# Analog_Input.net
KiCad netlist of a schematic drawn in Altium Designer
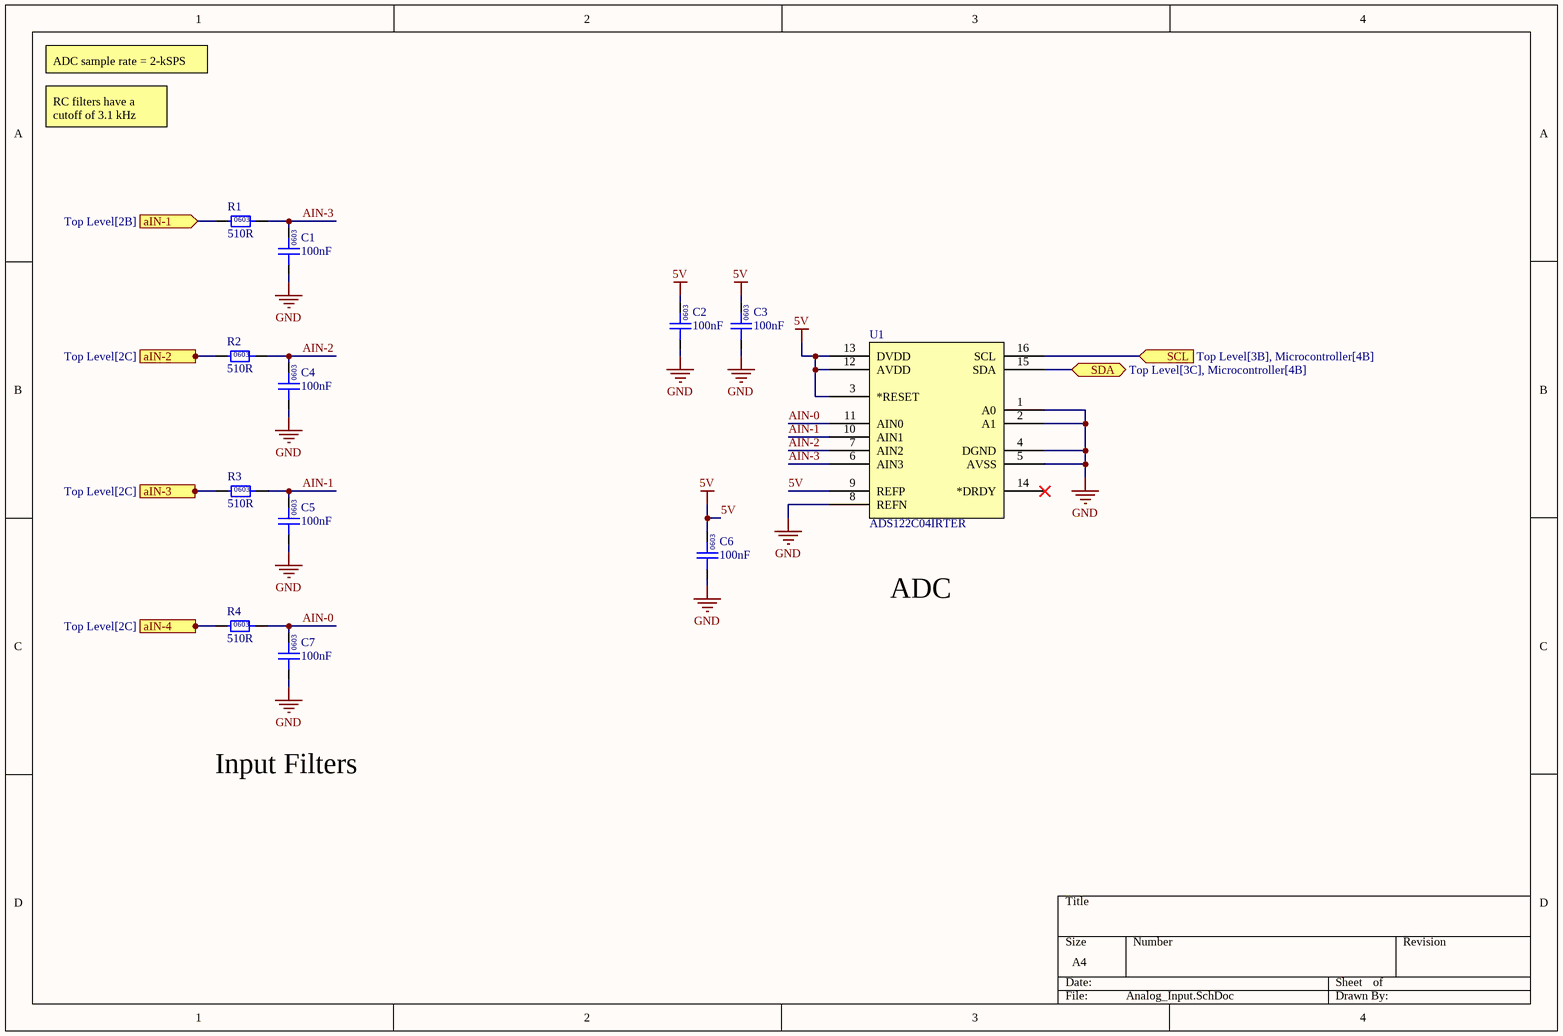
[diagram p0: Analog_Input.SchDoc]

(export (version "E")
  (design (tool "Eeschema 10.0.6"))
  (components
    (comp (ref "C1")
      (value "100nF")
      (footprint "0603")
      (fields
        (field (name "PART NUMBER") "GCM188L81H104KA57D")
        (field (name "MANUFACTURER") "muRata")
        (field (name "TOLERANCE") "±10%")
      )
      (libsource (lib "ts_standard_library") (part "Capacitor 0603"))
    )
    (comp (ref "C2")
      (value "100nF")
      (footprint "0603")
      (fields
        (field (name "PART NUMBER") "GCM188L81H104KA57D")
        (field (name "MANUFACTURER") "muRata")
        (field (name "TOLERANCE") "±10%")
      )
      (libsource (lib "ts_standard_library") (part "Capacitor 0603"))
    )
    (comp (ref "C3")
      (value "100nF")
      (footprint "0603")
      (fields
        (field (name "PART NUMBER") "GCM188L81H104KA57D")
        (field (name "MANUFACTURER") "muRata")
        (field (name "TOLERANCE") "±10%")
      )
      (libsource (lib "ts_standard_library") (part "Capacitor 0603"))
    )
    (comp (ref "C4")
      (value "100nF")
      (footprint "0603")
      (fields
        (field (name "PART NUMBER") "GCM188L81H104KA57D")
        (field (name "MANUFACTURER") "muRata")
        (field (name "TOLERANCE") "±10%")
      )
      (libsource (lib "ts_standard_library") (part "Capacitor 0603"))
    )
    (comp (ref "C5")
      (value "100nF")
      (footprint "0603")
      (fields
        (field (name "PART NUMBER") "GCM188L81H104KA57D")
        (field (name "MANUFACTURER") "muRata")
        (field (name "TOLERANCE") "±10%")
      )
      (libsource (lib "ts_standard_library") (part "Capacitor 0603"))
    )
    (comp (ref "C6")
      (value "100nF")
      (footprint "0603")
      (fields
        (field (name "PART NUMBER") "GCM188L81H104KA57D")
        (field (name "MANUFACTURER") "muRata")
        (field (name "TOLERANCE") "±10%")
      )
      (libsource (lib "ts_standard_library") (part "Capacitor 0603"))
    )
    (comp (ref "C7")
      (value "100nF")
      (footprint "0603")
      (fields
        (field (name "PART NUMBER") "GCM188L81H104KA57D")
        (field (name "MANUFACTURER") "muRata")
        (field (name "TOLERANCE") "±10%")
      )
      (libsource (lib "ts_standard_library") (part "Capacitor 0603"))
    )
    (comp (ref "R1")
      (value "510R")
      (footprint "0603")
      (fields
        (field (name "PART NUMBER") "RC0603FR-07510RL")
        (field (name "MANUFACTURER") "YAGEO")
        (field (name "TOLERANCE") "0.01")
      )
      (libsource (lib "ts_standard_library") (part "Resistor 0603"))
    )
    (comp (ref "R2")
      (value "510R")
      (footprint "0603")
      (fields
        (field (name "PART NUMBER") "RC0603FR-07510RL")
        (field (name "MANUFACTURER") "YAGEO")
        (field (name "TOLERANCE") "0.01")
      )
      (libsource (lib "ts_standard_library") (part "Resistor 0603"))
    )
    (comp (ref "R3")
      (value "510R")
      (footprint "0603")
      (fields
        (field (name "PART NUMBER") "RC0603FR-07510RL")
        (field (name "MANUFACTURER") "YAGEO")
        (field (name "TOLERANCE") "0.01")
      )
      (libsource (lib "ts_standard_library") (part "Resistor 0603"))
    )
    (comp (ref "R4")
      (value "510R")
      (footprint "0603")
      (fields
        (field (name "PART NUMBER") "RC0603FR-07510RL")
        (field (name "MANUFACTURER") "YAGEO")
        (field (name "TOLERANCE") "0.01")
      )
      (libsource (lib "ts_standard_library") (part "Resistor 0603"))
    )
    (comp (ref "U1")
      (value "ADS122C04IRTER")
      (footprint "TI 16-WQFN (3x3)")
      (description "IC ADC 24BIT SIGMA-DELTA 16WQFN")
      (fields
        (field (name "MANUFACTURER") "Texas Instruments")
        (field (name "DIGIKEY PART NUMBER") "296-50886-1-ND")
      )
      (libsource (lib "ts_standard_library") (part "ADS122C04IPW"))
    )
  )
  (nets
    (net (code "1") (name "/AIN-0") (class "Default")
      (node (ref "C7") (pin "2") (pinfunction "2_2") (pintype "passive"))
      (node (ref "R4") (pin "2") (pinfunction "2_2") (pintype "passive"))
      (node (ref "U1") (pin "11") (pinfunction "AIN0_11") (pintype "passive"))
    )
    (net (code "2") (name "/AIN-1") (class "Default")
      (node (ref "C5") (pin "2") (pinfunction "2_2") (pintype "passive"))
      (node (ref "R3") (pin "2") (pinfunction "2_2") (pintype "passive"))
      (node (ref "U1") (pin "10") (pinfunction "AIN1_10") (pintype "passive"))
    )
    (net (code "3") (name "/AIN-2") (class "Default")
      (node (ref "C4") (pin "2") (pinfunction "2_2") (pintype "passive"))
      (node (ref "R2") (pin "2") (pinfunction "2_2") (pintype "passive"))
      (node (ref "U1") (pin "7") (pinfunction "AIN2_7") (pintype "passive"))
    )
    (net (code "4") (name "/AIN-3") (class "Default")
      (node (ref "C1") (pin "2") (pinfunction "2_2") (pintype "passive"))
      (node (ref "R1") (pin "2") (pinfunction "2_2") (pintype "passive"))
      (node (ref "U1") (pin "6") (pinfunction "AIN3_6") (pintype "passive"))
    )
    (net (code "5") (name "/SCL") (class "Default")
      (node (ref "U1") (pin "16") (pinfunction "SCL_16") (pintype "passive"))
    )
    (net (code "6") (name "/SDA") (class "Default")
      (node (ref "U1") (pin "15") (pinfunction "SDA_15") (pintype "passive"))
    )
    (net (code "7") (name "/aIN-1") (class "Default")
      (node (ref "R1") (pin "1") (pinfunction "1_1") (pintype "passive"))
    )
    (net (code "8") (name "/aIN-2") (class "Default")
      (node (ref "R2") (pin "1") (pinfunction "1_1") (pintype "passive"))
    )
    (net (code "9") (name "/aIN-3") (class "Default")
      (node (ref "R3") (pin "1") (pinfunction "1_1") (pintype "passive"))
    )
    (net (code "10") (name "/aIN-4") (class "Default")
      (node (ref "R4") (pin "1") (pinfunction "1_1") (pintype "passive"))
    )
    (net (code "11") (name "5V") (class "Default")
      (node (ref "C2") (pin "2") (pinfunction "2_2") (pintype "passive"))
      (node (ref "C3") (pin "2") (pinfunction "2_2") (pintype "passive"))
      (node (ref "C6") (pin "2") (pinfunction "2_2") (pintype "passive"))
      (node (ref "U1") (pin "12") (pinfunction "AVDD_12") (pintype "passive"))
      (node (ref "U1") (pin "13") (pinfunction "DVDD_13") (pintype "passive"))
      (node (ref "U1") (pin "3") (pinfunction "*RESET_3") (pintype "passive"))
      (node (ref "U1") (pin "9") (pinfunction "REFP_9") (pintype "passive"))
    )
    (net (code "12") (name "GND") (class "Default")
      (node (ref "C1") (pin "1") (pinfunction "1_1") (pintype "passive"))
      (node (ref "C2") (pin "1") (pinfunction "1_1") (pintype "passive"))
      (node (ref "C3") (pin "1") (pinfunction "1_1") (pintype "passive"))
      (node (ref "C4") (pin "1") (pinfunction "1_1") (pintype "passive"))
      (node (ref "C5") (pin "1") (pinfunction "1_1") (pintype "passive"))
      (node (ref "C6") (pin "1") (pinfunction "1_1") (pintype "passive"))
      (node (ref "C7") (pin "1") (pinfunction "1_1") (pintype "passive"))
      (node (ref "U1") (pin "1") (pinfunction "A0_1") (pintype "passive"))
      (node (ref "U1") (pin "2") (pinfunction "A1_2") (pintype "passive"))
      (node (ref "U1") (pin "4") (pinfunction "DGND_4") (pintype "passive"))
      (node (ref "U1") (pin "5") (pinfunction "AVSS_5") (pintype "passive"))
      (node (ref "U1") (pin "8") (pinfunction "REFN_8") (pintype "passive"))
    )
    (net (code "13") (name "unconnected-(U1-*DRDY-Pad14)") (class "Default")
      (node (ref "U1") (pin "14") (pinfunction "*DRDY_14") (pintype "passive+no_connect"))
    )
  )
)
